# LED.net
KiCad netlist of a schematic drawn in Altium Designer
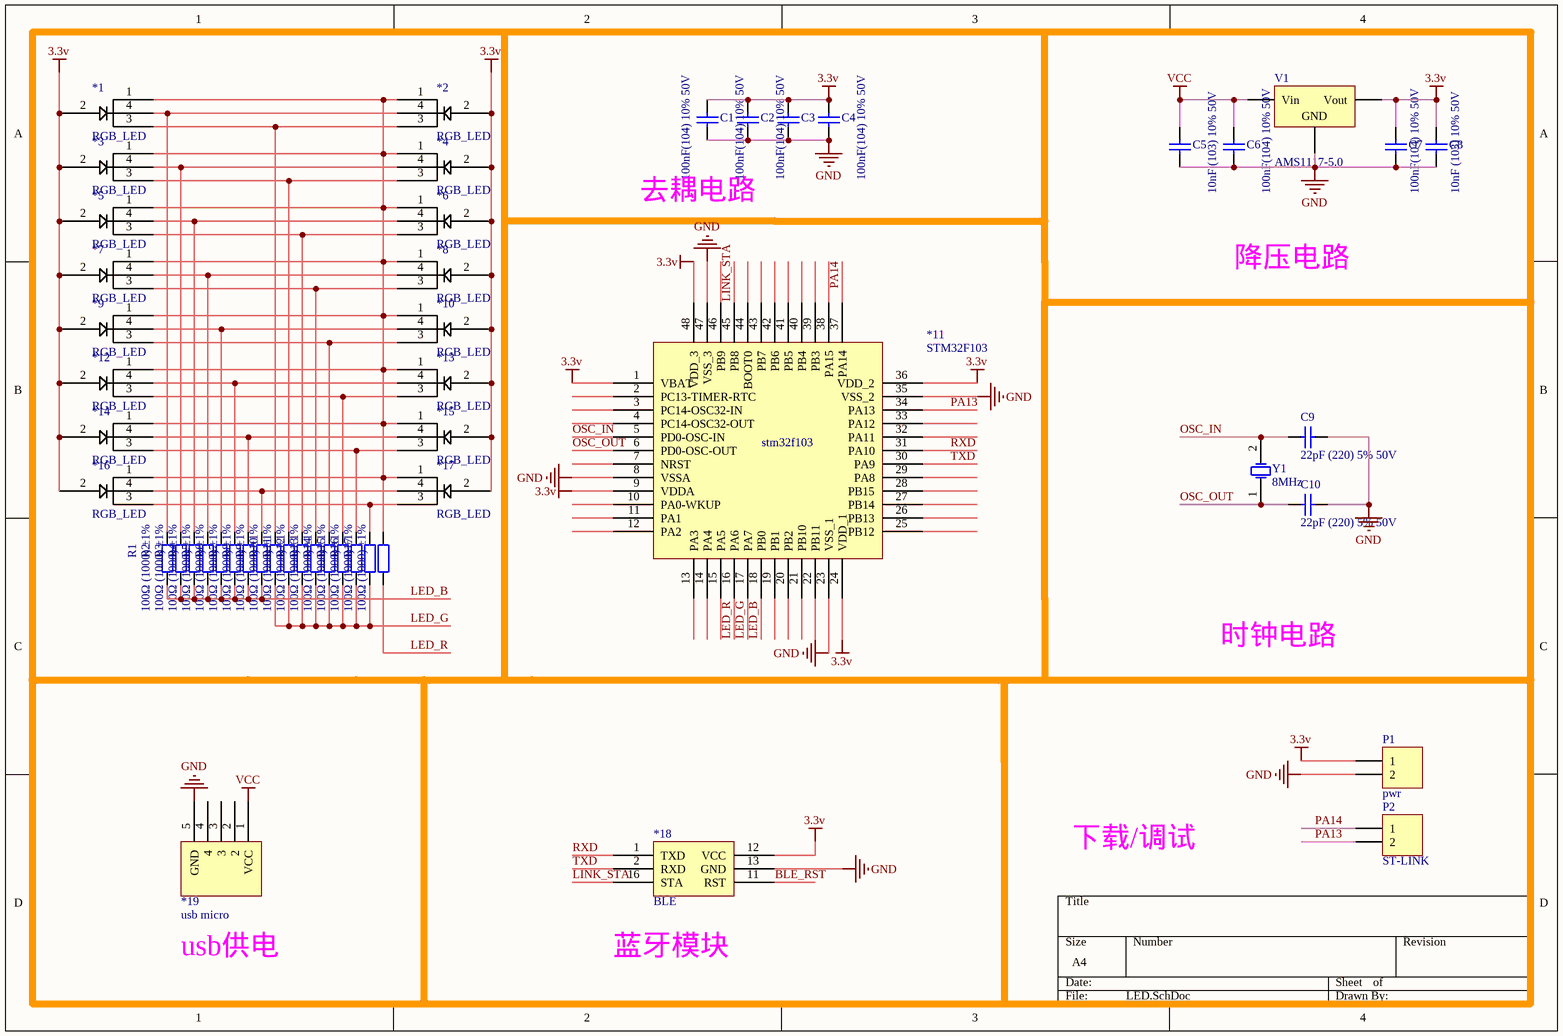
[diagram p0: LED.SchDoc]

(export (version "E")
  (design (tool "Eeschema 10.0.6"))
  (components
    (comp (ref "*1") (value "RGB_LED") (footprint "LED_RGB") (libsource (lib "LED") (part "RGB_LED")))
    (comp (ref "*2") (value "RGB_LED") (footprint "LED_RGB") (libsource (lib "LED") (part "RGB_LED")))
    (comp (ref "*3") (value "RGB_LED") (footprint "LED_RGB") (libsource (lib "LED") (part "RGB_LED")))
    (comp (ref "*4") (value "RGB_LED") (footprint "LED_RGB") (libsource (lib "LED") (part "RGB_LED")))
    (comp (ref "*5") (value "RGB_LED") (footprint "LED_RGB") (libsource (lib "LED") (part "RGB_LED")))
    (comp (ref "*6") (value "RGB_LED") (footprint "LED_RGB") (libsource (lib "LED") (part "RGB_LED")))
    (comp (ref "*7") (value "RGB_LED") (footprint "LED_RGB") (libsource (lib "LED") (part "RGB_LED")))
    (comp (ref "*8") (value "RGB_LED") (footprint "LED_RGB") (libsource (lib "LED") (part "RGB_LED")))
    (comp (ref "*9") (value "RGB_LED") (footprint "LED_RGB") (libsource (lib "LED") (part "RGB_LED")))
    (comp (ref "*10") (value "RGB_LED") (footprint "LED_RGB") (libsource (lib "LED") (part "RGB_LED")))
    (comp (ref "*11")
      (value "STM32F103")
      (footprint "STM32 C8T6")
      (libsource (lib "stm32f103") (part "STM32F103"))
    )
    (comp (ref "*12") (value "RGB_LED") (footprint "LED_RGB") (libsource (lib "LED") (part "RGB_LED")))
    (comp (ref "*13") (value "RGB_LED") (footprint "LED_RGB") (libsource (lib "LED") (part "RGB_LED")))
    (comp (ref "*14") (value "RGB_LED") (footprint "LED_RGB") (libsource (lib "LED") (part "RGB_LED")))
    (comp (ref "*15") (value "RGB_LED") (footprint "LED_RGB") (libsource (lib "LED") (part "RGB_LED")))
    (comp (ref "*16") (value "RGB_LED") (footprint "LED_RGB") (libsource (lib "LED") (part "RGB_LED")))
    (comp (ref "*17") (value "RGB_LED") (footprint "LED_RGB") (libsource (lib "LED") (part "RGB_LED")))
    (comp (ref "*18") (value "BLE") (footprint "BLE") (libsource (lib "LED") (part "BLE")))
    (comp (ref "*19")
      (value "usb micro")
      (footprint "MICRO_USB")
      (libsource (lib "altium-import") (part "root_3_usb micro_"))
    )
    (comp (ref "C1")
      (value "100nF(104) 10% 50V")
      (footprint "0805_C")
      (description "贴片电容")
      (libsource (lib "Miscellaneous Devices LC") (part "0805 100nF(104) 10% 50V"))
    )
    (comp (ref "C2")
      (value "100nF(104) 10% 50V")
      (footprint "0805_C")
      (description "贴片电容")
      (libsource (lib "Miscellaneous Devices LC") (part "0805 100nF(104) 10% 50V"))
    )
    (comp (ref "C3")
      (value "100nF(104) 10% 50V")
      (footprint "0805_C")
      (description "贴片电容")
      (libsource (lib "Miscellaneous Devices LC") (part "0805 100nF(104) 10% 50V"))
    )
    (comp (ref "C4")
      (value "100nF(104) 10% 50V")
      (footprint "0805_C")
      (description "贴片电容")
      (libsource (lib "Miscellaneous Devices LC") (part "0805 100nF(104) 10% 50V"))
    )
    (comp (ref "C5")
      (value "10nF (103) 10% 50V")
      (footprint "0805_C")
      (description "贴片电容")
      (libsource (lib "Miscellaneous Devices LC") (part "0805 10nF (103) 10% 50V"))
    )
    (comp (ref "C6")
      (value "100nF(104) 10% 50V")
      (footprint "0805_C")
      (description "贴片电容")
      (libsource (lib "Miscellaneous Devices LC") (part "0805 100nF(104) 10% 50V"))
    )
    (comp (ref "C7")
      (value "100nF(104) 10% 50V")
      (footprint "0805_C")
      (description "贴片电容")
      (libsource (lib "Miscellaneous Devices LC") (part "0805 100nF(104) 10% 50V"))
    )
    (comp (ref "C8")
      (value "10nF (103) 10% 50V")
      (footprint "0805_C")
      (description "贴片电容")
      (libsource (lib "Miscellaneous Devices LC") (part "0805 10nF (103) 10% 50V"))
    )
    (comp (ref "C9")
      (value "22pF (220) 5% 50V")
      (footprint "0805_C")
      (description "贴片电容")
      (libsource (lib "Miscellaneous Devices LC") (part "0805 22pF (220) 5% 50V"))
    )
    (comp (ref "C10")
      (value "22pF (220) 5% 50V")
      (footprint "0805_C")
      (description "贴片电容")
      (libsource (lib "Miscellaneous Devices LC") (part "0805 22pF (220) 5% 50V"))
    )
    (comp (ref "P1")
      (value "pwr")
      (footprint "HDR1X2")
      (description "Header, 2-Pin")
      (fields (field (name "PUBLISHER") "Altium Limited"))
      (libsource (lib "Miscellaneous Connectors") (part "Header 2"))
    )
    (comp (ref "P2")
      (value "ST-LINK")
      (footprint "HDR1X2")
      (description "Header, 2-Pin")
      (fields (field (name "PUBLISHER") "Altium Limited"))
      (libsource (lib "Miscellaneous Connectors") (part "Header 2"))
    )
    (comp (ref "R1")
      (value "100Ω (1000) ±1%")
      (footprint "0805_R")
      (description "贴片电阻")
      (libsource (lib "Miscellaneous Devices LC") (part "0805 100Ω (1000) 1%"))
    )
    (comp (ref "R2")
      (value "100Ω (1000) ±1%")
      (footprint "0805_R")
      (description "贴片电阻")
      (libsource (lib "Miscellaneous Devices LC") (part "0805 100Ω (1000) 1%"))
    )
    (comp (ref "R3")
      (value "100Ω (1000) ±1%")
      (footprint "0805_R")
      (description "贴片电阻")
      (libsource (lib "Miscellaneous Devices LC") (part "0805 100Ω (1000) 1%"))
    )
    (comp (ref "R4")
      (value "100Ω (1000) ±1%")
      (footprint "0805_R")
      (description "贴片电阻")
      (libsource (lib "Miscellaneous Devices LC") (part "0805 100Ω (1000) 1%"))
    )
    (comp (ref "R5")
      (value "100Ω (1000) ±1%")
      (footprint "0805_R")
      (description "贴片电阻")
      (libsource (lib "Miscellaneous Devices LC") (part "0805 100Ω (1000) 1%"))
    )
    (comp (ref "R6")
      (value "100Ω (1000) ±1%")
      (footprint "0805_R")
      (description "贴片电阻")
      (libsource (lib "Miscellaneous Devices LC") (part "0805 100Ω (1000) 1%"))
    )
    (comp (ref "R7")
      (value "100Ω (1000) ±1%")
      (footprint "0805_R")
      (description "贴片电阻")
      (libsource (lib "Miscellaneous Devices LC") (part "0805 100Ω (1000) 1%"))
    )
    (comp (ref "R8")
      (value "100Ω (1000) ±1%")
      (footprint "0805_R")
      (description "贴片电阻")
      (libsource (lib "Miscellaneous Devices LC") (part "0805 100Ω (1000) 1%"))
    )
    (comp (ref "R9")
      (value "100Ω (1000) ±1%")
      (footprint "0805_R")
      (description "贴片电阻")
      (libsource (lib "Miscellaneous Devices LC") (part "0805 100Ω (1000) 1%"))
    )
    (comp (ref "R10")
      (value "100Ω (1000) ±1%")
      (footprint "0805_R")
      (description "贴片电阻")
      (libsource (lib "Miscellaneous Devices LC") (part "0805 100Ω (1000) 1%"))
    )
    (comp (ref "R11")
      (value "100Ω (1000) ±1%")
      (footprint "0805_R")
      (description "贴片电阻")
      (libsource (lib "Miscellaneous Devices LC") (part "0805 100Ω (1000) 1%"))
    )
    (comp (ref "R12")
      (value "100Ω (1000) ±1%")
      (footprint "0805_R")
      (description "贴片电阻")
      (libsource (lib "Miscellaneous Devices LC") (part "0805 100Ω (1000) 1%"))
    )
    (comp (ref "R13")
      (value "100Ω (1000) ±1%")
      (footprint "0805_R")
      (description "贴片电阻")
      (libsource (lib "Miscellaneous Devices LC") (part "0805 100Ω (1000) 1%"))
    )
    (comp (ref "R14")
      (value "100Ω (1000) ±1%")
      (footprint "0805_R")
      (description "贴片电阻")
      (libsource (lib "Miscellaneous Devices LC") (part "0805 100Ω (1000) 1%"))
    )
    (comp (ref "R15")
      (value "100Ω (1000) ±1%")
      (footprint "0805_R")
      (description "贴片电阻")
      (libsource (lib "Miscellaneous Devices LC") (part "0805 100Ω (1000) 1%"))
    )
    (comp (ref "R16")
      (value "100Ω (1000) ±1%")
      (footprint "0805_R")
      (description "贴片电阻")
      (libsource (lib "Miscellaneous Devices LC") (part "0805 100Ω (1000) 1%"))
    )
    (comp (ref "R17")
      (value "100Ω (1000) ±1%")
      (footprint "0805_R")
      (description "贴片电阻")
      (libsource (lib "Miscellaneous Devices LC") (part "0805 100Ω (1000) 1%"))
    )
    (comp (ref "V1")
      (value "AMS1117-5.0")
      (footprint "SOT-223")
      (description "低压差线性稳压(LDO)")
      (libsource (lib "Miscellaneous Devices LC") (part "SOT-223 AMS1117-5.0"))
    )
    (comp (ref "Y1")
      (value "8MHz")
      (footprint "XTAL_US")
      (description "Crystal Oscillator")
      (fields (field (name "PUBLISHER") "Altium Limited"))
      (libsource (lib "Explorer STM32F407封装库") (part "XTAL"))
    )
  )
  (nets
    (net (code "1") (name "/BLE_RST") (class "Default")
      (node (ref "*18") (pin "11") (pinfunction "RST_11") (pintype "passive"))
    )
    (net (code "2") (name "/LED_B") (class "Default")
      (node (ref "*11") (pin "18") (pinfunction "PB0_18") (pintype "passive"))
      (node (ref "R1") (pin "2") (pinfunction "2_2") (pintype "passive"))
      (node (ref "R2") (pin "2") (pinfunction "2_2") (pintype "passive"))
      (node (ref "R3") (pin "2") (pinfunction "2_2") (pintype "passive"))
      (node (ref "R4") (pin "2") (pinfunction "2_2") (pintype "passive"))
      (node (ref "R5") (pin "2") (pinfunction "2_2") (pintype "passive"))
      (node (ref "R6") (pin "2") (pinfunction "2_2") (pintype "passive"))
      (node (ref "R7") (pin "2") (pinfunction "2_2") (pintype "passive"))
      (node (ref "R8") (pin "2") (pinfunction "2_2") (pintype "passive"))
    )
    (net (code "3") (name "/LED_G") (class "Default")
      (node (ref "*11") (pin "17") (pinfunction "PA7_17") (pintype "passive"))
      (node (ref "R10") (pin "2") (pinfunction "2_2") (pintype "passive"))
      (node (ref "R11") (pin "2") (pinfunction "2_2") (pintype "passive"))
      (node (ref "R12") (pin "2") (pinfunction "2_2") (pintype "passive"))
      (node (ref "R13") (pin "2") (pinfunction "2_2") (pintype "passive"))
      (node (ref "R14") (pin "2") (pinfunction "2_2") (pintype "passive"))
      (node (ref "R15") (pin "2") (pinfunction "2_2") (pintype "passive"))
      (node (ref "R16") (pin "2") (pinfunction "2_2") (pintype "passive"))
      (node (ref "R9") (pin "2") (pinfunction "2_2") (pintype "passive"))
    )
    (net (code "4") (name "/LED_R") (class "Default")
      (node (ref "*11") (pin "16") (pinfunction "PA6_16") (pintype "passive"))
      (node (ref "R17") (pin "2") (pinfunction "2_2") (pintype "passive"))
    )
    (net (code "5") (name "/LINK_STA") (class "Default")
      (node (ref "*11") (pin "45") (pinfunction "PB8_45") (pintype "passive"))
      (node (ref "*18") (pin "16") (pinfunction "STA_16") (pintype "passive"))
    )
    (net (code "6") (name "/OSC_IN") (class "Default")
      (node (ref "*11") (pin "5") (pinfunction "PD0-OSC-IN_5") (pintype "passive"))
      (node (ref "C9") (pin "1") (pinfunction "1_1") (pintype "passive"))
      (node (ref "Y1") (pin "2") (pinfunction "OSC2_2") (pintype "passive"))
    )
    (net (code "7") (name "/OSC_OUT") (class "Default")
      (node (ref "*11") (pin "6") (pinfunction "PD0-OSC-OUT_6") (pintype "passive"))
      (node (ref "C10") (pin "1") (pinfunction "1_1") (pintype "passive"))
      (node (ref "Y1") (pin "1") (pinfunction "OSC1_1") (pintype "passive"))
    )
    (net (code "8") (name "/PA13") (class "Default")
      (node (ref "*11") (pin "34") (pinfunction "PA13_34") (pintype "passive"))
      (node (ref "P2") (pin "2") (pinfunction "2_2") (pintype "passive"))
    )
    (net (code "9") (name "/PA14") (class "Default")
      (node (ref "*11") (pin "37") (pinfunction "PA14_37") (pintype "passive"))
      (node (ref "P2") (pin "1") (pinfunction "1_1") (pintype "passive"))
    )
    (net (code "10") (name "/RXD") (class "Default")
      (node (ref "*11") (pin "31") (pinfunction "PA10_31") (pintype "passive"))
      (node (ref "*18") (pin "1") (pinfunction "TXD_1") (pintype "passive"))
    )
    (net (code "11") (name "/TXD") (class "Default")
      (node (ref "*11") (pin "30") (pinfunction "PA9_30") (pintype "passive"))
      (node (ref "*18") (pin "2") (pinfunction "RXD_2") (pintype "passive"))
    )
    (net (code "12") (name "3.3v") (class "Default")
      (node (ref "*1") (pin "2") (pintype "passive"))
      (node (ref "*10") (pin "2") (pintype "passive"))
      (node (ref "*11") (pin "1") (pinfunction "VBAT_1") (pintype "passive"))
      (node (ref "*11") (pin "24") (pinfunction "VDD_1_24") (pintype "passive"))
      (node (ref "*11") (pin "36") (pinfunction "VDD_2_36") (pintype "passive"))
      (node (ref "*11") (pin "48") (pinfunction "VDD_3_48") (pintype "passive"))
      (node (ref "*11") (pin "9") (pinfunction "VDDA_9") (pintype "passive"))
      (node (ref "*12") (pin "2") (pintype "passive"))
      (node (ref "*13") (pin "2") (pintype "passive"))
      (node (ref "*14") (pin "2") (pintype "passive"))
      (node (ref "*15") (pin "2") (pintype "passive"))
      (node (ref "*16") (pin "2") (pintype "passive"))
      (node (ref "*17") (pin "2") (pintype "passive"))
      (node (ref "*18") (pin "12") (pinfunction "VCC_12") (pintype "passive"))
      (node (ref "*2") (pin "2") (pintype "passive"))
      (node (ref "*3") (pin "2") (pintype "passive"))
      (node (ref "*4") (pin "2") (pintype "passive"))
      (node (ref "*5") (pin "2") (pintype "passive"))
      (node (ref "*6") (pin "2") (pintype "passive"))
      (node (ref "*7") (pin "2") (pintype "passive"))
      (node (ref "*8") (pin "2") (pintype "passive"))
      (node (ref "*9") (pin "2") (pintype "passive"))
      (node (ref "C1") (pin "2") (pinfunction "2_2") (pintype "passive"))
      (node (ref "C2") (pin "2") (pinfunction "2_2") (pintype "passive"))
      (node (ref "C3") (pin "2") (pinfunction "2_2") (pintype "passive"))
      (node (ref "C4") (pin "2") (pinfunction "2_2") (pintype "passive"))
      (node (ref "C7") (pin "2") (pinfunction "2_2") (pintype "passive"))
      (node (ref "C8") (pin "2") (pinfunction "2_2") (pintype "passive"))
      (node (ref "P1") (pin "1") (pinfunction "1_1") (pintype "passive"))
      (node (ref "V1") (pin "2") (pinfunction "Vout_2") (pintype "passive"))
    )
    (net (code "13") (name "GND") (class "Default")
      (node (ref "*11") (pin "23") (pinfunction "VSS_1_23") (pintype "passive"))
      (node (ref "*11") (pin "35") (pinfunction "VSS_2_35") (pintype "passive"))
      (node (ref "*11") (pin "47") (pinfunction "VSS_3_47") (pintype "passive"))
      (node (ref "*11") (pin "8") (pinfunction "VSSA_8") (pintype "passive"))
      (node (ref "*18") (pin "13") (pinfunction "GND_13") (pintype "passive"))
      (node (ref "*19") (pin "5") (pinfunction "GND_5") (pintype "passive"))
      (node (ref "C1") (pin "1") (pinfunction "1_1") (pintype "passive"))
      (node (ref "C10") (pin "2") (pinfunction "2_2") (pintype "passive"))
      (node (ref "C2") (pin "1") (pinfunction "1_1") (pintype "passive"))
      (node (ref "C3") (pin "1") (pinfunction "1_1") (pintype "passive"))
      (node (ref "C4") (pin "1") (pinfunction "1_1") (pintype "passive"))
      (node (ref "C5") (pin "1") (pinfunction "1_1") (pintype "passive"))
      (node (ref "C6") (pin "1") (pinfunction "1_1") (pintype "passive"))
      (node (ref "C7") (pin "1") (pinfunction "1_1") (pintype "passive"))
      (node (ref "C8") (pin "1") (pinfunction "1_1") (pintype "passive"))
      (node (ref "C9") (pin "2") (pinfunction "2_2") (pintype "passive"))
      (node (ref "P1") (pin "2") (pinfunction "2_2") (pintype "passive"))
      (node (ref "V1") (pin "1") (pinfunction "GND_1") (pintype "passive"))
    )
    (net (code "14") (name "Net-(*1-Pad1)") (class "Default")
      (node (ref "*1") (pin "1") (pintype "passive"))
      (node (ref "*10") (pin "1") (pintype "passive"))
      (node (ref "*12") (pin "1") (pintype "passive"))
      (node (ref "*13") (pin "1") (pintype "passive"))
      (node (ref "*14") (pin "1") (pintype "passive"))
      (node (ref "*15") (pin "1") (pintype "passive"))
      (node (ref "*16") (pin "1") (pintype "passive"))
      (node (ref "*17") (pin "1") (pintype "passive"))
      (node (ref "*2") (pin "1") (pintype "passive"))
      (node (ref "*3") (pin "1") (pintype "passive"))
      (node (ref "*4") (pin "1") (pintype "passive"))
      (node (ref "*5") (pin "1") (pintype "passive"))
      (node (ref "*6") (pin "1") (pintype "passive"))
      (node (ref "*7") (pin "1") (pintype "passive"))
      (node (ref "*8") (pin "1") (pintype "passive"))
      (node (ref "*9") (pin "1") (pintype "passive"))
      (node (ref "R17") (pin "1") (pinfunction "1_1") (pintype "passive"))
    )
    (net (code "15") (name "Net-(*1-Pad3)") (class "Default")
      (node (ref "*1") (pin "3") (pintype "passive"))
      (node (ref "*2") (pin "3") (pintype "passive"))
      (node (ref "R9") (pin "1") (pinfunction "1_1") (pintype "passive"))
    )
    (net (code "16") (name "Net-(*1-Pad4)") (class "Default")
      (node (ref "*1") (pin "4") (pintype "passive"))
      (node (ref "*2") (pin "4") (pintype "passive"))
      (node (ref "R1") (pin "1") (pinfunction "1_1") (pintype "passive"))
    )
    (net (code "17") (name "Net-(*3-Pad3)") (class "Default")
      (node (ref "*3") (pin "3") (pintype "passive"))
      (node (ref "*4") (pin "3") (pintype "passive"))
      (node (ref "R10") (pin "1") (pinfunction "1_1") (pintype "passive"))
    )
    (net (code "18") (name "Net-(*3-Pad4)") (class "Default")
      (node (ref "*3") (pin "4") (pintype "passive"))
      (node (ref "*4") (pin "4") (pintype "passive"))
      (node (ref "R2") (pin "1") (pinfunction "1_1") (pintype "passive"))
    )
    (net (code "19") (name "Net-(*5-Pad3)") (class "Default")
      (node (ref "*5") (pin "3") (pintype "passive"))
      (node (ref "*6") (pin "3") (pintype "passive"))
      (node (ref "R11") (pin "1") (pinfunction "1_1") (pintype "passive"))
    )
    (net (code "20") (name "Net-(*5-Pad4)") (class "Default")
      (node (ref "*5") (pin "4") (pintype "passive"))
      (node (ref "*6") (pin "4") (pintype "passive"))
      (node (ref "R3") (pin "1") (pinfunction "1_1") (pintype "passive"))
    )
    (net (code "21") (name "Net-(*7-Pad3)") (class "Default")
      (node (ref "*7") (pin "3") (pintype "passive"))
      (node (ref "*8") (pin "3") (pintype "passive"))
      (node (ref "R12") (pin "1") (pinfunction "1_1") (pintype "passive"))
    )
    (net (code "22") (name "Net-(*7-Pad4)") (class "Default")
      (node (ref "*7") (pin "4") (pintype "passive"))
      (node (ref "*8") (pin "4") (pintype "passive"))
      (node (ref "R4") (pin "1") (pinfunction "1_1") (pintype "passive"))
    )
    (net (code "23") (name "Net-(*10-Pad3)") (class "Default")
      (node (ref "*10") (pin "3") (pintype "passive"))
      (node (ref "*9") (pin "3") (pintype "passive"))
      (node (ref "R13") (pin "1") (pinfunction "1_1") (pintype "passive"))
    )
    (net (code "24") (name "Net-(*10-Pad4)") (class "Default")
      (node (ref "*10") (pin "4") (pintype "passive"))
      (node (ref "*9") (pin "4") (pintype "passive"))
      (node (ref "R5") (pin "1") (pinfunction "1_1") (pintype "passive"))
    )
    (net (code "25") (name "Net-(*12-Pad3)") (class "Default")
      (node (ref "*12") (pin "3") (pintype "passive"))
      (node (ref "*13") (pin "3") (pintype "passive"))
      (node (ref "R14") (pin "1") (pinfunction "1_1") (pintype "passive"))
    )
    (net (code "26") (name "Net-(*12-Pad4)") (class "Default")
      (node (ref "*12") (pin "4") (pintype "passive"))
      (node (ref "*13") (pin "4") (pintype "passive"))
      (node (ref "R6") (pin "1") (pinfunction "1_1") (pintype "passive"))
    )
    (net (code "27") (name "Net-(*14-Pad3)") (class "Default")
      (node (ref "*14") (pin "3") (pintype "passive"))
      (node (ref "*15") (pin "3") (pintype "passive"))
      (node (ref "R15") (pin "1") (pinfunction "1_1") (pintype "passive"))
    )
    (net (code "28") (name "Net-(*14-Pad4)") (class "Default")
      (node (ref "*14") (pin "4") (pintype "passive"))
      (node (ref "*15") (pin "4") (pintype "passive"))
      (node (ref "R7") (pin "1") (pinfunction "1_1") (pintype "passive"))
    )
    (net (code "29") (name "Net-(*16-Pad3)") (class "Default")
      (node (ref "*16") (pin "3") (pintype "passive"))
      (node (ref "*17") (pin "3") (pintype "passive"))
      (node (ref "R16") (pin "1") (pinfunction "1_1") (pintype "passive"))
    )
    (net (code "30") (name "Net-(*16-Pad4)") (class "Default")
      (node (ref "*16") (pin "4") (pintype "passive"))
      (node (ref "*17") (pin "4") (pintype "passive"))
      (node (ref "R8") (pin "1") (pinfunction "1_1") (pintype "passive"))
    )
    (net (code "31") (name "VCC") (class "Default")
      (node (ref "*19") (pin "1") (pinfunction "VCC_1") (pintype "passive"))
      (node (ref "C5") (pin "2") (pinfunction "2_2") (pintype "passive"))
      (node (ref "C6") (pin "2") (pinfunction "2_2") (pintype "passive"))
      (node (ref "V1") (pin "3") (pinfunction "Vin_3") (pintype "passive"))
    )
    (net (code "32") (name "unconnected-(*11-BOOT0-Pad44)") (class "Default")
      (node (ref "*11") (pin "44") (pinfunction "BOOT0_44") (pintype "passive"))
    )
    (net (code "33") (name "unconnected-(*11-NRST-Pad7)") (class "Default")
      (node (ref "*11") (pin "7") (pinfunction "NRST_7") (pintype "passive"))
    )
    (net (code "34") (name "unconnected-(*11-PA0-WKUP-Pad10)") (class "Default")
      (node (ref "*11") (pin "10") (pinfunction "PA0-WKUP_10") (pintype "passive"))
    )
    (net (code "35") (name "unconnected-(*11-PA1-Pad11)") (class "Default")
      (node (ref "*11") (pin "11") (pinfunction "PA1_11") (pintype "passive"))
    )
    (net (code "36") (name "unconnected-(*11-PA2-Pad12)") (class "Default")
      (node (ref "*11") (pin "12") (pinfunction "PA2_12") (pintype "passive"))
    )
    (net (code "37") (name "unconnected-(*11-PA3-Pad13)") (class "Default")
      (node (ref "*11") (pin "13") (pinfunction "PA3_13") (pintype "passive"))
    )
    (net (code "38") (name "unconnected-(*11-PA4-Pad14)") (class "Default")
      (node (ref "*11") (pin "14") (pinfunction "PA4_14") (pintype "passive"))
    )
    (net (code "39") (name "unconnected-(*11-PA5-Pad15)") (class "Default")
      (node (ref "*11") (pin "15") (pinfunction "PA5_15") (pintype "passive"))
    )
    (net (code "40") (name "unconnected-(*11-PA8-Pad29)") (class "Default")
      (node (ref "*11") (pin "29") (pinfunction "PA8_29") (pintype "passive"))
    )
    (net (code "41") (name "unconnected-(*11-PA11-Pad32)") (class "Default")
      (node (ref "*11") (pin "32") (pinfunction "PA11_32") (pintype "passive"))
    )
    (net (code "42") (name "unconnected-(*11-PA12-Pad33)") (class "Default")
      (node (ref "*11") (pin "33") (pinfunction "PA12_33") (pintype "passive"))
    )
    (net (code "43") (name "unconnected-(*11-PA15-Pad38)") (class "Default")
      (node (ref "*11") (pin "38") (pinfunction "PA15_38") (pintype "passive"))
    )
    (net (code "44") (name "unconnected-(*11-PB1-Pad19)") (class "Default")
      (node (ref "*11") (pin "19") (pinfunction "PB1_19") (pintype "passive"))
    )
    (net (code "45") (name "unconnected-(*11-PB2-Pad20)") (class "Default")
      (node (ref "*11") (pin "20") (pinfunction "PB2_20") (pintype "passive"))
    )
    (net (code "46") (name "unconnected-(*11-PB3-Pad39)") (class "Default")
      (node (ref "*11") (pin "39") (pinfunction "PB3_39") (pintype "passive"))
    )
    (net (code "47") (name "unconnected-(*11-PB4-Pad40)") (class "Default")
      (node (ref "*11") (pin "40") (pinfunction "PB4_40") (pintype "passive"))
    )
    (net (code "48") (name "unconnected-(*11-PB5-Pad41)") (class "Default")
      (node (ref "*11") (pin "41") (pinfunction "PB5_41") (pintype "passive"))
    )
    (net (code "49") (name "unconnected-(*11-PB6-Pad42)") (class "Default")
      (node (ref "*11") (pin "42") (pinfunction "PB6_42") (pintype "passive"))
    )
    (net (code "50") (name "unconnected-(*11-PB7-Pad43)") (class "Default")
      (node (ref "*11") (pin "43") (pinfunction "PB7_43") (pintype "passive"))
    )
    (net (code "51") (name "unconnected-(*11-PB9-Pad46)") (class "Default")
      (node (ref "*11") (pin "46") (pinfunction "PB9_46") (pintype "passive"))
    )
    (net (code "52") (name "unconnected-(*11-PB10-Pad21)") (class "Default")
      (node (ref "*11") (pin "21") (pinfunction "PB10_21") (pintype "passive"))
    )
    (net (code "53") (name "unconnected-(*11-PB11-Pad22)") (class "Default")
      (node (ref "*11") (pin "22") (pinfunction "PB11_22") (pintype "passive"))
    )
    (net (code "54") (name "unconnected-(*11-PB12-Pad25)") (class "Default")
      (node (ref "*11") (pin "25") (pinfunction "PB12_25") (pintype "passive"))
    )
    (net (code "55") (name "unconnected-(*11-PB13-Pad26)") (class "Default")
      (node (ref "*11") (pin "26") (pinfunction "PB13_26") (pintype "passive"))
    )
    (net (code "56") (name "unconnected-(*11-PB14-Pad27)") (class "Default")
      (node (ref "*11") (pin "27") (pinfunction "PB14_27") (pintype "passive"))
    )
    (net (code "57") (name "unconnected-(*11-PB15-Pad28)") (class "Default")
      (node (ref "*11") (pin "28") (pinfunction "PB15_28") (pintype "passive"))
    )
    (net (code "58") (name "unconnected-(*11-PC13-TIMER-RTC-Pad2)") (class "Default")
      (node (ref "*11") (pin "2") (pinfunction "PC13-TIMER-RTC_2") (pintype "passive"))
    )
    (net (code "59") (name "unconnected-(*11-PC14-OSC32-IN-Pad3)") (class "Default")
      (node (ref "*11") (pin "3") (pinfunction "PC14-OSC32-IN_3") (pintype "passive"))
    )
    (net (code "60") (name "unconnected-(*11-PC14-OSC32-OUT-Pad4)") (class "Default")
      (node (ref "*11") (pin "4") (pinfunction "PC14-OSC32-OUT_4") (pintype "passive"))
    )
    (net (code "61") (name "unconnected-(*19-Pad2)") (class "Default")
      (node (ref "*19") (pin "2") (pinfunction "2_2") (pintype "passive"))
    )
    (net (code "62") (name "unconnected-(*19-Pad3)") (class "Default")
      (node (ref "*19") (pin "3") (pinfunction "3_3") (pintype "passive"))
    )
    (net (code "63") (name "unconnected-(*19-Pad4)") (class "Default")
      (node (ref "*19") (pin "4") (pinfunction "4_4") (pintype "passive"))
    )
  )
)
